# SC8701_EVM_RE0.net
KiCad netlist of a schematic drawn in Altium Designer
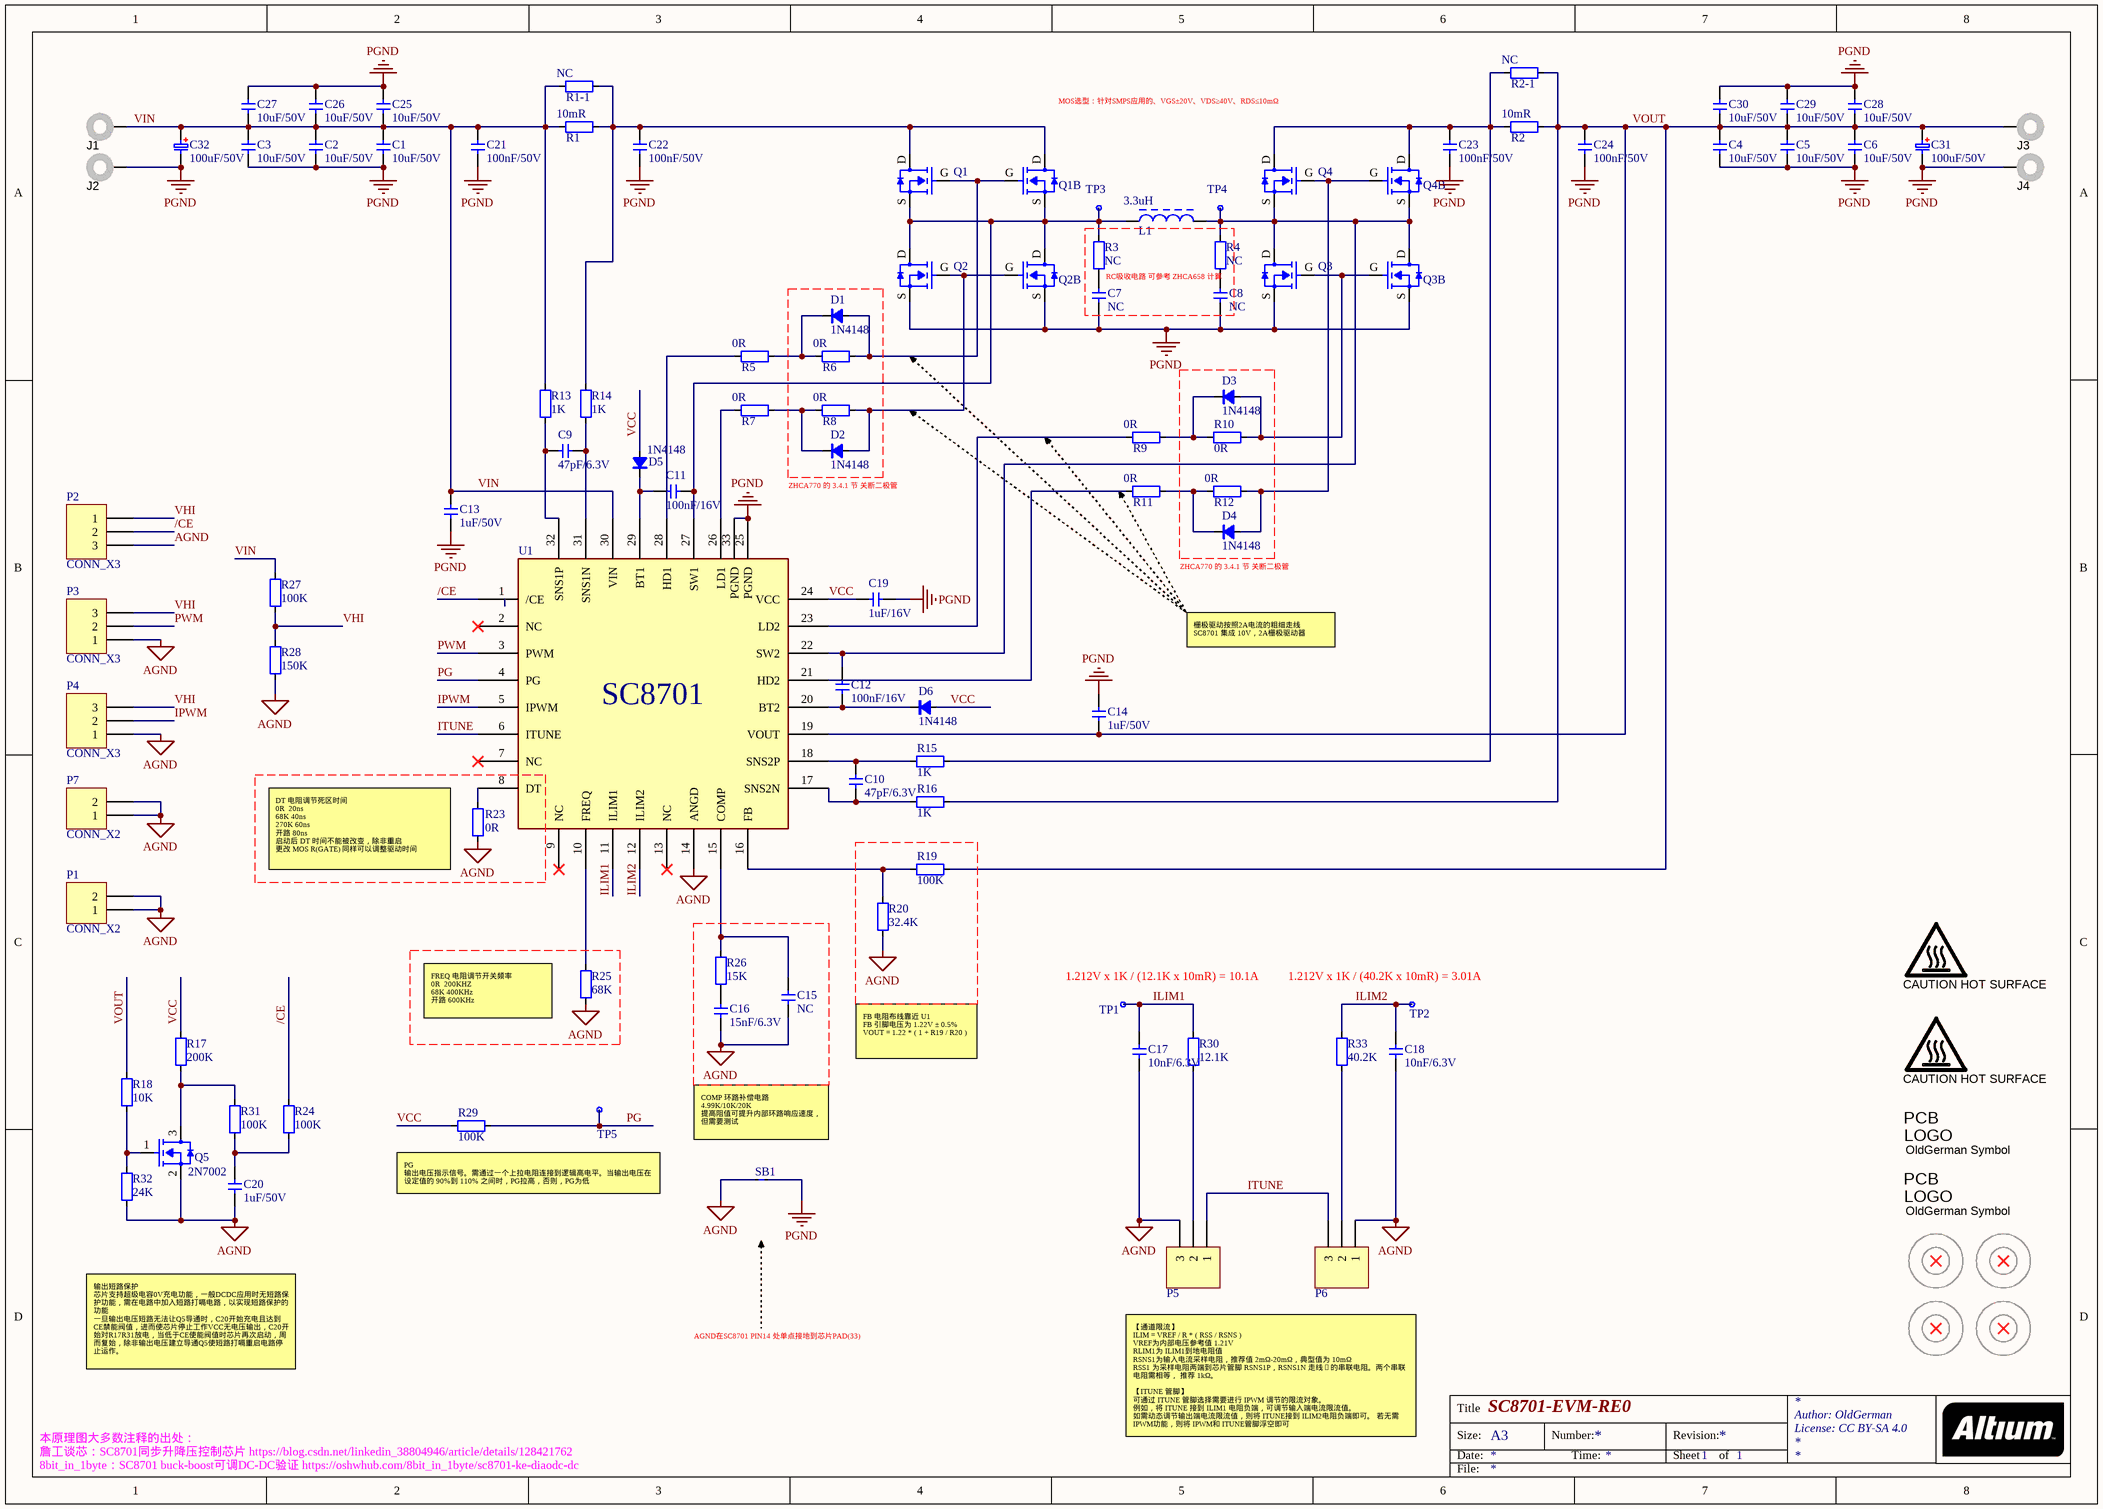
[diagram p0: SC8701_EVM_RE0.SchDoc]

(export (version "E")
  (design (tool "Eeschema 10.0.6"))
  (components
    (comp (ref "C1")
      (value "10uF/50V")
      (footprint "C1206")
      (description "Capacitor")
      (libsource (lib "ODG_AD_Lib") (part "CAP"))
    )
    (comp (ref "C2")
      (value "10uF/50V")
      (footprint "C1206")
      (description "Capacitor")
      (libsource (lib "ODG_AD_Lib") (part "CAP"))
    )
    (comp (ref "C3")
      (value "10uF/50V")
      (footprint "C1206")
      (description "Capacitor")
      (libsource (lib "ODG_AD_Lib") (part "CAP"))
    )
    (comp (ref "C4")
      (value "10uF/50V")
      (footprint "C1206")
      (description "Capacitor")
      (libsource (lib "ODG_AD_Lib") (part "CAP"))
    )
    (comp (ref "C5")
      (value "10uF/50V")
      (footprint "C1206")
      (description "Capacitor")
      (libsource (lib "ODG_AD_Lib") (part "CAP"))
    )
    (comp (ref "C6")
      (value "10uF/50V")
      (footprint "C1206")
      (description "Capacitor")
      (libsource (lib "ODG_AD_Lib") (part "CAP"))
    )
    (comp (ref "C7")
      (value "NC")
      (footprint "C0603")
      (description "Capacitor")
      (libsource (lib "ODG_AD_Lib") (part "CAP"))
    )
    (comp (ref "C8")
      (value "NC")
      (footprint "C0603")
      (description "Capacitor")
      (libsource (lib "ODG_AD_Lib") (part "CAP"))
    )
    (comp (ref "C9")
      (value "47pF/6.3V")
      (footprint "C0603")
      (description "Capacitor")
      (libsource (lib "ODG_AD_Lib") (part "CAP"))
    )
    (comp (ref "C10")
      (value "47pF/6.3V")
      (footprint "C0603")
      (description "Capacitor")
      (libsource (lib "ODG_AD_Lib") (part "CAP"))
    )
    (comp (ref "C11")
      (value "100nF/16V")
      (footprint "C0603")
      (description "Capacitor")
      (libsource (lib "ODG_AD_Lib") (part "CAP"))
    )
    (comp (ref "C12")
      (value "100nF/16V")
      (footprint "C0603")
      (description "Capacitor")
      (libsource (lib "ODG_AD_Lib") (part "CAP"))
    )
    (comp (ref "C13")
      (value "1uF/50V")
      (footprint "C0603")
      (description "Capacitor")
      (libsource (lib "ODG_AD_Lib") (part "CAP"))
    )
    (comp (ref "C14")
      (value "1uF/50V")
      (footprint "C0603")
      (description "Capacitor")
      (libsource (lib "ODG_AD_Lib") (part "CAP"))
    )
    (comp (ref "C15")
      (value "NC")
      (footprint "C0603")
      (description "Capacitor")
      (libsource (lib "ODG_AD_Lib") (part "CAP"))
    )
    (comp (ref "C16")
      (value "15nF/6.3V")
      (footprint "C0603")
      (description "Capacitor")
      (libsource (lib "ODG_AD_Lib") (part "CAP"))
    )
    (comp (ref "C17")
      (value "10nF/6.3V")
      (footprint "C0603")
      (description "Capacitor")
      (libsource (lib "ODG_AD_Lib") (part "CAP"))
    )
    (comp (ref "C18")
      (value "10nF/6.3V")
      (footprint "C0603")
      (description "Capacitor")
      (libsource (lib "ODG_AD_Lib") (part "CAP"))
    )
    (comp (ref "C19")
      (value "1uF/16V")
      (footprint "C0603")
      (description "Capacitor")
      (libsource (lib "ODG_AD_Lib") (part "CAP"))
    )
    (comp (ref "C20")
      (value "1uF/50V")
      (footprint "C0603")
      (description "Capacitor")
      (libsource (lib "ODG_AD_Lib") (part "CAP"))
    )
    (comp (ref "C21")
      (value "100nF/50V")
      (footprint "C0603")
      (description "Capacitor")
      (libsource (lib "ODG_AD_Lib") (part "CAP"))
    )
    (comp (ref "C22")
      (value "100nF/50V")
      (footprint "C0603")
      (description "Capacitor")
      (libsource (lib "ODG_AD_Lib") (part "CAP"))
    )
    (comp (ref "C23")
      (value "100nF/50V")
      (footprint "C0603")
      (description "Capacitor")
      (libsource (lib "ODG_AD_Lib") (part "CAP"))
    )
    (comp (ref "C24")
      (value "100nF/50V")
      (footprint "C0603")
      (description "Capacitor")
      (libsource (lib "ODG_AD_Lib") (part "CAP"))
    )
    (comp (ref "C25")
      (value "10uF/50V")
      (footprint "C1206")
      (description "Capacitor")
      (libsource (lib "ODG_AD_Lib") (part "CAP"))
    )
    (comp (ref "C26")
      (value "10uF/50V")
      (footprint "C1206")
      (description "Capacitor")
      (libsource (lib "ODG_AD_Lib") (part "CAP"))
    )
    (comp (ref "C27")
      (value "10uF/50V")
      (footprint "C1206")
      (description "Capacitor")
      (libsource (lib "ODG_AD_Lib") (part "CAP"))
    )
    (comp (ref "C28")
      (value "10uF/50V")
      (footprint "C1206")
      (description "Capacitor")
      (libsource (lib "ODG_AD_Lib") (part "CAP"))
    )
    (comp (ref "C29")
      (value "10uF/50V")
      (footprint "C1206")
      (description "Capacitor")
      (libsource (lib "ODG_AD_Lib") (part "CAP"))
    )
    (comp (ref "C30")
      (value "10uF/50V")
      (footprint "C1206")
      (description "Capacitor")
      (libsource (lib "ODG_AD_Lib") (part "CAP"))
    )
    (comp (ref "C31")
      (value "100uF/50V")
      (footprint "CAP OS-CON D=10.0 L=10.0 F10")
      (description "Capacitor")
      (libsource (lib "ODG_AD_Lib") (part "CAP_Polar_Aluminum"))
    )
    (comp (ref "C32")
      (value "100uF/50V")
      (footprint "CAP OS-CON D=10.0 L=10.0 F10")
      (description "Capacitor")
      (libsource (lib "ODG_AD_Lib") (part "CAP_Polar_Aluminum"))
    )
    (comp (ref "D1")
      (value "1N4148")
      (footprint "SOD-323")
      (description "二极管")
      (libsource (lib "ODG_AD_Lib") (part "DIODE"))
    )
    (comp (ref "D2")
      (value "1N4148")
      (footprint "SOD-323")
      (description "二极管")
      (libsource (lib "ODG_AD_Lib") (part "DIODE"))
    )
    (comp (ref "D3")
      (value "1N4148")
      (footprint "SOD-323")
      (description "二极管")
      (libsource (lib "ODG_AD_Lib") (part "DIODE"))
    )
    (comp (ref "D4")
      (value "1N4148")
      (footprint "SOD-323")
      (description "二极管")
      (libsource (lib "ODG_AD_Lib") (part "DIODE"))
    )
    (comp (ref "D5")
      (value "1N4148")
      (footprint "SOD-323")
      (description "二极管")
      (libsource (lib "") (part "DIODE_1"))
    )
    (comp (ref "D6")
      (value "1N4148")
      (footprint "SOD-323")
      (description "二极管")
      (libsource (lib "ODG_AD_Lib") (part "DIODE"))
    )
    (comp (ref "H1") (value "HOLE") (footprint "M3.2 D=8") (libsource (lib "ODG_AD_Lib") (part "HOLE")))
    (comp (ref "H2") (value "HOLE") (footprint "M3.2 D=8") (libsource (lib "ODG_AD_Lib") (part "HOLE")))
    (comp (ref "H3") (value "HOLE") (footprint "M3.2 D=8") (libsource (lib "ODG_AD_Lib") (part "HOLE")))
    (comp (ref "H4") (value "HOLE") (footprint "M3.2 D=8") (libsource (lib "ODG_AD_Lib") (part "HOLE")))
    (comp (ref "J1")
      (value "U6047")
      (footprint "JACK_BANANA_U6047")
      (description "Banana Jack")
      (fields
        (field (name "PARTNUMBER") "575-8")
        (field (name "MANUFACTURER") "Keystone")
        (field (name "PUBLISHER") "Texas Instruments")
      )
      (libsource (lib "ODG_AD_Lib") (part "JACK_BANANA"))
    )
    (comp (ref "J2")
      (value "U6047")
      (footprint "JACK_BANANA_U6047")
      (description "Banana Jack")
      (fields
        (field (name "PARTNUMBER") "575-8")
        (field (name "MANUFACTURER") "Keystone")
        (field (name "PUBLISHER") "Texas Instruments")
      )
      (libsource (lib "ODG_AD_Lib") (part "JACK_BANANA"))
    )
    (comp (ref "J3")
      (value "U6047")
      (footprint "JACK_BANANA_U6047")
      (description "Banana Jack")
      (fields
        (field (name "PARTNUMBER") "575-8")
        (field (name "MANUFACTURER") "Keystone")
        (field (name "PUBLISHER") "Texas Instruments")
      )
      (libsource (lib "ODG_AD_Lib") (part "JACK_BANANA"))
    )
    (comp (ref "J4")
      (value "U6047")
      (footprint "JACK_BANANA_U6047")
      (description "Banana Jack")
      (fields
        (field (name "PARTNUMBER") "575-8")
        (field (name "MANUFACTURER") "Keystone")
        (field (name "PUBLISHER") "Texas Instruments")
      )
      (libsource (lib "ODG_AD_Lib") (part "JACK_BANANA"))
    )
    (comp (ref "L1")
      (value "3.3uH")
      (footprint "INDUCTOR 1350 12.6X13.5X5.0mm")
      (description "135 功率电感 额定电流15A")
      (libsource (lib "ODG_AD_Lib") (part "Inductor_power"))
    )
    (comp (ref "LOGO1")
      (value "CAUTION HOT SURFACE")
      (footprint "IEC_HotSurface_Small")
      (description "IEC 61010-1 Hot Surface Warning")
      (fields (field (name "SYMBOLCREATOR") "a0412235") (field (name "PUBLISHER") "Texas Instruments"))
      (libsource (lib "ODG_AD_Lib") (part "IEC_HotSurface"))
    )
    (comp (ref "LOGO2")
      (value "CAUTION HOT SURFACE")
      (footprint "IEC_HotSurface_Small")
      (description "IEC 61010-1 Hot Surface Warning")
      (fields (field (name "SYMBOLCREATOR") "a0412235") (field (name "PUBLISHER") "Texas Instruments"))
      (libsource (lib "ODG_AD_Lib") (part "IEC_HotSurface"))
    )
    (comp (ref "Logo3")
      (value "OldGerman Symbol")
      (footprint "ODG_LOGO")
      (fields (field (name "SYMBOLCREATOR") "a0412235") (field (name "PUBLISHER") "Texas Instruments"))
      (libsource (lib "ODG_AD_Lib") (part "OldGeman"))
    )
    (comp (ref "Logo4")
      (value "OldGerman Symbol")
      (footprint "ODG_LOGO")
      (fields (field (name "SYMBOLCREATOR") "a0412235") (field (name "PUBLISHER") "Texas Instruments"))
      (libsource (lib "ODG_AD_Lib") (part "OldGeman"))
    )
    (comp (ref "P1")
      (value "CONN_X2")
      (footprint "2.54mm_Male_x2")
      (libsource (lib "ODG_AD_Lib") (part "CONN_X2"))
    )
    (comp (ref "P2")
      (value "CONN_X3")
      (footprint "2.54mm_Male_x3")
      (libsource (lib "ODG_AD_Lib") (part "CONN_X3"))
    )
    (comp (ref "P3") (value "CONN_X3") (footprint "2.54mm_Male_x3") (libsource (lib "") (part "CONN_X3_1")))
    (comp (ref "P4") (value "CONN_X3") (footprint "2.54mm_Male_x3") (libsource (lib "") (part "CONN_X3_1")))
    (comp (ref "P5")
      (value "CONN_X3")
      (footprint "2.54mm_Male_x3")
      (libsource (lib "ODG_AD_Lib") (part "CONN_X3"))
    )
    (comp (ref "P6")
      (value "CONN_X3")
      (footprint "2.54mm_Male_x3")
      (libsource (lib "ODG_AD_Lib") (part "CONN_X3"))
    )
    (comp (ref "P7")
      (value "CONN_X2")
      (footprint "2.54mm_Male_x2")
      (libsource (lib "ODG_AD_Lib") (part "CONN_X2"))
    )
    (comp (ref "Q1")
      (value "N-MOS_GDS")
      (footprint "SON 3X3 NexFET Q3")
      (libsource (lib "ODG_AD_Lib") (part "N-MOS_GDS"))
    )
    (comp (ref "Q1B")
      (value "N-MOS_GDS")
      (footprint "SO8FL ROUND")
      (libsource (lib "ODG_AD_Lib") (part "N-MOS_GDS"))
    )
    (comp (ref "Q2")
      (value "N-MOS_GDS")
      (footprint "SON 3X3 NexFET Q3")
      (libsource (lib "ODG_AD_Lib") (part "N-MOS_GDS"))
    )
    (comp (ref "Q2B")
      (value "N-MOS_GDS")
      (footprint "SO8FL ROUND")
      (libsource (lib "ODG_AD_Lib") (part "N-MOS_GDS"))
    )
    (comp (ref "Q3")
      (value "N-MOS_GDS")
      (footprint "SON 3X3 NexFET Q3")
      (libsource (lib "ODG_AD_Lib") (part "N-MOS_GDS"))
    )
    (comp (ref "Q3B")
      (value "N-MOS_GDS")
      (footprint "SO8FL ROUND")
      (libsource (lib "ODG_AD_Lib") (part "N-MOS_GDS"))
    )
    (comp (ref "Q4")
      (value "N-MOS_GDS")
      (footprint "SON 3X3 NexFET Q3")
      (libsource (lib "ODG_AD_Lib") (part "N-MOS_GDS"))
    )
    (comp (ref "Q4B")
      (value "N-MOS_GDS")
      (footprint "SO8FL ROUND")
      (libsource (lib "ODG_AD_Lib") (part "N-MOS_GDS"))
    )
    (comp (ref "Q5")
      (value "2N7002")
      (footprint "INFINEON SOT-23-3")
      (description "N-MOS")
      (libsource (lib "ODG_AD_Lib") (part "N-MOS_123"))
    )
    (comp (ref "R1")
      (value "10mR")
      (footprint "R1206")
      (description "IEC Standard")
      (libsource (lib "ODG_AD_Lib") (part "RES"))
    )
    (comp (ref "R1-1")
      (value "NC")
      (footprint "R1206")
      (description "IEC Standard")
      (libsource (lib "ODG_AD_Lib") (part "RES"))
    )
    (comp (ref "R2")
      (value "10mR")
      (footprint "R1206")
      (description "IEC Standard")
      (libsource (lib "ODG_AD_Lib") (part "RES"))
    )
    (comp (ref "R2-1")
      (value "NC")
      (footprint "R1206")
      (description "IEC Standard")
      (libsource (lib "ODG_AD_Lib") (part "RES"))
    )
    (comp (ref "R3")
      (value "NC")
      (footprint "R0805")
      (description "IEC Standard")
      (libsource (lib "") (part "RES_1"))
    )
    (comp (ref "R4")
      (value "NC")
      (footprint "R0805")
      (description "IEC Standard")
      (libsource (lib "") (part "RES_1"))
    )
    (comp (ref "R5")
      (value "0R")
      (footprint "R0603")
      (description "IEC Standard")
      (libsource (lib "ODG_AD_Lib") (part "RES"))
    )
    (comp (ref "R6")
      (value "0R")
      (footprint "R0603")
      (description "IEC Standard")
      (libsource (lib "ODG_AD_Lib") (part "RES"))
    )
    (comp (ref "R7")
      (value "0R")
      (footprint "R0603")
      (description "IEC Standard")
      (libsource (lib "ODG_AD_Lib") (part "RES"))
    )
    (comp (ref "R8")
      (value "0R")
      (footprint "R0603")
      (description "IEC Standard")
      (libsource (lib "ODG_AD_Lib") (part "RES"))
    )
    (comp (ref "R9")
      (value "0R")
      (footprint "R0603")
      (description "IEC Standard")
      (libsource (lib "ODG_AD_Lib") (part "RES"))
    )
    (comp (ref "R10")
      (value "0R")
      (footprint "R0603")
      (description "IEC Standard")
      (libsource (lib "ODG_AD_Lib") (part "RES"))
    )
    (comp (ref "R11")
      (value "0R")
      (footprint "R0603")
      (description "IEC Standard")
      (libsource (lib "ODG_AD_Lib") (part "RES"))
    )
    (comp (ref "R12")
      (value "0R")
      (footprint "R0603")
      (description "IEC Standard")
      (libsource (lib "ODG_AD_Lib") (part "RES"))
    )
    (comp (ref "R13")
      (value "1K")
      (footprint "R0603")
      (description "IEC Standard")
      (libsource (lib "") (part "RES_1"))
    )
    (comp (ref "R14")
      (value "1K")
      (footprint "R0603")
      (description "IEC Standard")
      (libsource (lib "") (part "RES_1"))
    )
    (comp (ref "R15")
      (value "1K")
      (footprint "R0603")
      (description "IEC Standard")
      (libsource (lib "") (part "RES_2"))
    )
    (comp (ref "R16")
      (value "1K")
      (footprint "R0603")
      (description "IEC Standard")
      (libsource (lib "") (part "RES_2"))
    )
    (comp (ref "R17")
      (value "200K")
      (footprint "R0603")
      (description "IEC Standard")
      (libsource (lib "") (part "RES_1"))
    )
    (comp (ref "R18")
      (value "10K")
      (footprint "R0603")
      (description "IEC Standard")
      (libsource (lib "") (part "RES_1"))
    )
    (comp (ref "R19")
      (value "100K")
      (footprint "R0603")
      (description "IEC Standard")
      (libsource (lib "ODG_AD_Lib") (part "RES"))
    )
    (comp (ref "R20")
      (value "32.4K")
      (footprint "R0603")
      (description "IEC Standard")
      (libsource (lib "") (part "RES_1"))
    )
    (comp (ref "R23")
      (value "0R")
      (footprint "R0603")
      (description "IEC Standard")
      (libsource (lib "") (part "RES_1"))
    )
    (comp (ref "R24")
      (value "100K")
      (footprint "R0603")
      (description "IEC Standard")
      (libsource (lib "") (part "RES_1"))
    )
    (comp (ref "R25")
      (value "68K")
      (footprint "R0603")
      (description "IEC Standard")
      (libsource (lib "") (part "RES_1"))
    )
    (comp (ref "R26")
      (value "15K")
      (footprint "R0603")
      (description "IEC Standard")
      (libsource (lib "") (part "RES_1"))
    )
    (comp (ref "R27")
      (value "100K")
      (footprint "R0603")
      (description "IEC Standard")
      (libsource (lib "") (part "RES_1"))
    )
    (comp (ref "R28")
      (value "150K")
      (footprint "R0603")
      (description "IEC Standard")
      (libsource (lib "") (part "RES_1"))
    )
    (comp (ref "R29")
      (value "100K")
      (footprint "R0603")
      (description "IEC Standard")
      (libsource (lib "ODG_AD_Lib") (part "RES"))
    )
    (comp (ref "R30")
      (value "12.1K")
      (footprint "R0603")
      (description "IEC Standard")
      (libsource (lib "") (part "RES_1"))
    )
    (comp (ref "R31")
      (value "100K")
      (footprint "R0603")
      (description "IEC Standard")
      (libsource (lib "") (part "RES_1"))
    )
    (comp (ref "R32")
      (value "24K")
      (footprint "R0603")
      (description "IEC Standard")
      (libsource (lib "") (part "RES_1"))
    )
    (comp (ref "R33")
      (value "40.2K")
      (footprint "R0603")
      (description "IEC Standard")
      (libsource (lib "") (part "RES_1"))
    )
    (comp (ref "SB1")
      (value "NetTie_200um")
      (footprint "NetTie_200um")
      (description "Net Tie")
      (fields (field (name "PART NUMBER") "NetTie 0.2mm") (field (name "PUBLISHER") "Nordic Semiconductor"))
      (libsource (lib "pca63100") (part "NetTie 0.2mm"))
    )
    (comp (ref "TP1")
      (value "CONN_X1_DOT")
      (footprint "2.54mm_Male_x1")
      (libsource (lib "ODG_AD_Lib") (part "CONN_X1_DOT"))
    )
    (comp (ref "TP2")
      (value "CONN_X1_DOT")
      (footprint "2.54mm_Male_x1")
      (libsource (lib "ODG_AD_Lib") (part "CONN_X1_DOT"))
    )
    (comp (ref "TP3")
      (value "CONN_X1_DOT")
      (footprint "2.54mm_Male_x1")
      (libsource (lib "ODG_AD_Lib") (part "CONN_X1_DOT"))
    )
    (comp (ref "TP4")
      (value "CONN_X1_DOT")
      (footprint "2.54mm_Male_x1")
      (libsource (lib "ODG_AD_Lib") (part "CONN_X1_DOT"))
    )
    (comp (ref "TP5")
      (value "CONN_X1_DOT")
      (footprint "2.54mm_Male_x1")
      (libsource (lib "ODG_AD_Lib") (part "CONN_X1_DOT"))
    )
    (comp (ref "U1")
      (value "SC8701 (A)")
      (footprint "TQFN-32 4X4MM 0.4 VIA")
      (description "高效率, 同步, 4 管升降压控制器")
      (libsource (lib "ODG_AD_Lib") (part "SC8701 (A)"))
    )
  )
  (nets
    (net (code "1") (name "/ILIM1") (class "Default")
      (node (ref "C17") (pin "2") (pinfunction "2_2") (pintype "passive"))
      (node (ref "R30") (pin "2") (pinfunction "2_2") (pintype "passive"))
      (node (ref "TP1") (pin "1") (pinfunction "1_1") (pintype "passive"))
      (node (ref "U1") (pin "11") (pinfunction "ILIM1_11") (pintype "passive"))
    )
    (net (code "2") (name "/ILIM2") (class "Default")
      (node (ref "C18") (pin "2") (pinfunction "2_2") (pintype "passive"))
      (node (ref "R33") (pin "2") (pinfunction "2_2") (pintype "passive"))
      (node (ref "TP2") (pin "1") (pinfunction "1_1") (pintype "passive"))
      (node (ref "U1") (pin "12") (pinfunction "ILIM2_12") (pintype "passive"))
    )
    (net (code "3") (name "/IPWM") (class "Default")
      (node (ref "P4") (pin "2") (pinfunction "2_2") (pintype "passive"))
      (node (ref "U1") (pin "5") (pinfunction "IPWM_5") (pintype "passive"))
    )
    (net (code "4") (name "/ITUNE") (class "Default")
      (node (ref "P5") (pin "1") (pinfunction "1_1") (pintype "passive"))
      (node (ref "P6") (pin "3") (pinfunction "3_3") (pintype "passive"))
      (node (ref "U1") (pin "6") (pinfunction "ITUNE_6") (pintype "passive"))
    )
    (net (code "5") (name "/PG") (class "Default")
      (node (ref "R29") (pin "2") (pinfunction "2_2") (pintype "passive"))
      (node (ref "TP5") (pin "1") (pinfunction "1_1") (pintype "passive"))
      (node (ref "U1") (pin "4") (pinfunction "PG_4") (pintype "passive"))
    )
    (net (code "6") (name "/PWM") (class "Default")
      (node (ref "P3") (pin "2") (pinfunction "2_2") (pintype "passive"))
      (node (ref "U1") (pin "3") (pinfunction "PWM_3") (pintype "passive"))
    )
    (net (code "7") (name "/VCC") (class "Default")
      (node (ref "C19") (pin "1") (pinfunction "1_1") (pintype "passive"))
      (node (ref "D5") (pin "1") (pinfunction "A_1") (pintype "passive"))
      (node (ref "D6") (pin "1") (pinfunction "A_1") (pintype "passive"))
      (node (ref "R17") (pin "2") (pinfunction "2_2") (pintype "passive"))
      (node (ref "R29") (pin "1") (pinfunction "1_1") (pintype "passive"))
      (node (ref "U1") (pin "24") (pinfunction "VCC_24") (pintype "passive"))
    )
    (net (code "8") (name "/VHI") (class "Default")
      (node (ref "P2") (pin "1") (pinfunction "1_1") (pintype "passive"))
      (node (ref "P3") (pin "3") (pinfunction "3_3") (pintype "passive"))
      (node (ref "P4") (pin "3") (pinfunction "3_3") (pintype "passive"))
      (node (ref "R27") (pin "1") (pinfunction "1_1") (pintype "passive"))
      (node (ref "R28") (pin "2") (pinfunction "2_2") (pintype "passive"))
    )
    (net (code "9") (name "/VIN") (class "Default")
      (node (ref "C1") (pin "2") (pinfunction "2_2") (pintype "passive"))
      (node (ref "C13") (pin "1") (pinfunction "1_1") (pintype "passive"))
      (node (ref "C2") (pin "2") (pinfunction "2_2") (pintype "passive"))
      (node (ref "C21") (pin "2") (pinfunction "2_2") (pintype "passive"))
      (node (ref "C25") (pin "2") (pinfunction "2_2") (pintype "passive"))
      (node (ref "C26") (pin "2") (pinfunction "2_2") (pintype "passive"))
      (node (ref "C27") (pin "2") (pinfunction "2_2") (pintype "passive"))
      (node (ref "C3") (pin "2") (pinfunction "2_2") (pintype "passive"))
      (node (ref "C32") (pin "1") (pinfunction "1_1") (pintype "passive"))
      (node (ref "J1") (pin "1") (pinfunction "1_1") (pintype "passive"))
      (node (ref "R1") (pin "1") (pinfunction "1_1") (pintype "passive"))
      (node (ref "R1-1") (pin "1") (pinfunction "1_1") (pintype "passive"))
      (node (ref "R13") (pin "2") (pinfunction "2_2") (pintype "passive"))
      (node (ref "R27") (pin "2") (pinfunction "2_2") (pintype "passive"))
      (node (ref "U1") (pin "30") (pinfunction "VIN_30") (pintype "passive"))
    )
    (net (code "10") (name "/VOUT") (class "Default")
      (node (ref "C14") (pin "1") (pinfunction "1_1") (pintype "passive"))
      (node (ref "C24") (pin "2") (pinfunction "2_2") (pintype "passive"))
      (node (ref "C28") (pin "2") (pinfunction "2_2") (pintype "passive"))
      (node (ref "C29") (pin "2") (pinfunction "2_2") (pintype "passive"))
      (node (ref "C30") (pin "2") (pinfunction "2_2") (pintype "passive"))
      (node (ref "C31") (pin "1") (pinfunction "1_1") (pintype "passive"))
      (node (ref "C4") (pin "2") (pinfunction "2_2") (pintype "passive"))
      (node (ref "C5") (pin "2") (pinfunction "2_2") (pintype "passive"))
      (node (ref "C6") (pin "2") (pinfunction "2_2") (pintype "passive"))
      (node (ref "J3") (pin "1") (pinfunction "1_1") (pintype "passive"))
      (node (ref "R16") (pin "1") (pinfunction "1_1") (pintype "passive"))
      (node (ref "R18") (pin "2") (pinfunction "2_2") (pintype "passive"))
      (node (ref "R19") (pin "2") (pinfunction "2_2") (pintype "passive"))
      (node (ref "R2") (pin "2") (pinfunction "2_2") (pintype "passive"))
      (node (ref "R2-1") (pin "2") (pinfunction "2_2") (pintype "passive"))
      (node (ref "U1") (pin "19") (pinfunction "VOUT_19") (pintype "passive"))
    )
    (net (code "11") (name "/{slash}CE") (class "Default")
      (node (ref "P2") (pin "2") (pinfunction "2_2") (pintype "passive"))
      (node (ref "R24") (pin "2") (pinfunction "2_2") (pintype "passive"))
      (node (ref "U1") (pin "1") (pinfunction "/CE_1") (pintype "passive"))
    )
    (net (code "12") (name "AGND") (class "Default")
      (node (ref "C15") (pin "1") (pinfunction "1_1") (pintype "passive"))
      (node (ref "C16") (pin "1") (pinfunction "1_1") (pintype "passive"))
      (node (ref "C17") (pin "1") (pinfunction "1_1") (pintype "passive"))
      (node (ref "C18") (pin "1") (pinfunction "1_1") (pintype "passive"))
      (node (ref "C20") (pin "2") (pinfunction "2_2") (pintype "passive"))
      (node (ref "P1") (pin "1") (pinfunction "1_1") (pintype "passive"))
      (node (ref "P1") (pin "2") (pinfunction "2_2") (pintype "passive"))
      (node (ref "P2") (pin "3") (pinfunction "3_3") (pintype "passive"))
      (node (ref "P3") (pin "1") (pinfunction "1_1") (pintype "passive"))
      (node (ref "P4") (pin "1") (pinfunction "1_1") (pintype "passive"))
      (node (ref "P5") (pin "3") (pinfunction "3_3") (pintype "passive"))
      (node (ref "P6") (pin "1") (pinfunction "1_1") (pintype "passive"))
      (node (ref "P7") (pin "1") (pinfunction "1_1") (pintype "passive"))
      (node (ref "P7") (pin "2") (pinfunction "2_2") (pintype "passive"))
      (node (ref "Q5") (pin "2") (pinfunction "S_2") (pintype "passive"))
      (node (ref "R20") (pin "1") (pinfunction "1_1") (pintype "passive"))
      (node (ref "R23") (pin "1") (pinfunction "1_1") (pintype "passive"))
      (node (ref "R25") (pin "1") (pinfunction "1_1") (pintype "passive"))
      (node (ref "R28") (pin "1") (pinfunction "1_1") (pintype "passive"))
      (node (ref "R32") (pin "1") (pinfunction "1_1") (pintype "passive"))
      (node (ref "SB1") (pin "1") (pinfunction "1_1") (pintype "passive"))
      (node (ref "U1") (pin "14") (pinfunction "ANGD_14") (pintype "passive"))
    )
    (net (code "13") (name "Net-(C7-Pad2)") (class "Default")
      (node (ref "C7") (pin "2") (pinfunction "2_2") (pintype "passive"))
      (node (ref "R3") (pin "1") (pinfunction "1_1") (pintype "passive"))
    )
    (net (code "14") (name "Net-(C8-Pad2)") (class "Default")
      (node (ref "C8") (pin "2") (pinfunction "2_2") (pintype "passive"))
      (node (ref "R4") (pin "1") (pinfunction "1_1") (pintype "passive"))
    )
    (net (code "15") (name "Net-(C16-Pad2)") (class "Default")
      (node (ref "C16") (pin "2") (pinfunction "2_2") (pintype "passive"))
      (node (ref "R26") (pin "1") (pinfunction "1_1") (pintype "passive"))
    )
    (net (code "16") (name "Net-(C20-Pad1)") (class "Default")
      (node (ref "C20") (pin "1") (pinfunction "1_1") (pintype "passive"))
      (node (ref "R24") (pin "1") (pinfunction "1_1") (pintype "passive"))
      (node (ref "R31") (pin "1") (pinfunction "1_1") (pintype "passive"))
    )
    (net (code "17") (name "Net-(C22-Pad2)") (class "Default")
      (node (ref "C22") (pin "2") (pinfunction "2_2") (pintype "passive"))
      (node (ref "Q1") (pin "D") (pinfunction "D_D") (pintype "passive"))
      (node (ref "Q1B") (pin "D") (pinfunction "D_D") (pintype "passive"))
      (node (ref "R1") (pin "2") (pinfunction "2_2") (pintype "passive"))
      (node (ref "R1-1") (pin "2") (pinfunction "2_2") (pintype "passive"))
      (node (ref "R14") (pin "2") (pinfunction "2_2") (pintype "passive"))
    )
    (net (code "18") (name "Net-(C23-Pad2)") (class "Default")
      (node (ref "C23") (pin "2") (pinfunction "2_2") (pintype "passive"))
      (node (ref "Q4") (pin "D") (pinfunction "D_D") (pintype "passive"))
      (node (ref "Q4B") (pin "D") (pinfunction "D_D") (pintype "passive"))
      (node (ref "R15") (pin "1") (pinfunction "1_1") (pintype "passive"))
      (node (ref "R2") (pin "1") (pinfunction "1_1") (pintype "passive"))
      (node (ref "R2-1") (pin "1") (pinfunction "1_1") (pintype "passive"))
    )
    (net (code "19") (name "Net-(D1-A)") (class "Default")
      (node (ref "D1") (pin "1") (pinfunction "A_1") (pintype "passive"))
      (node (ref "Q1") (pin "G") (pinfunction "G_G") (pintype "passive"))
      (node (ref "Q1B") (pin "G") (pinfunction "G_G") (pintype "passive"))
      (node (ref "R6") (pin "2") (pinfunction "2_2") (pintype "passive"))
    )
    (net (code "20") (name "Net-(D1-C)") (class "Default")
      (node (ref "D1") (pin "2") (pinfunction "C_2") (pintype "passive"))
      (node (ref "R5") (pin "2") (pinfunction "2_2") (pintype "passive"))
      (node (ref "R6") (pin "1") (pinfunction "1_1") (pintype "passive"))
    )
    (net (code "21") (name "Net-(D2-A)") (class "Default")
      (node (ref "D2") (pin "1") (pinfunction "A_1") (pintype "passive"))
      (node (ref "Q2") (pin "G") (pinfunction "G_G") (pintype "passive"))
      (node (ref "Q2B") (pin "G") (pinfunction "G_G") (pintype "passive"))
      (node (ref "R8") (pin "2") (pinfunction "2_2") (pintype "passive"))
    )
    (net (code "22") (name "Net-(D2-C)") (class "Default")
      (node (ref "D2") (pin "2") (pinfunction "C_2") (pintype "passive"))
      (node (ref "R7") (pin "2") (pinfunction "2_2") (pintype "passive"))
      (node (ref "R8") (pin "1") (pinfunction "1_1") (pintype "passive"))
    )
    (net (code "23") (name "Net-(D3-A)") (class "Default")
      (node (ref "D3") (pin "1") (pinfunction "A_1") (pintype "passive"))
      (node (ref "Q3") (pin "G") (pinfunction "G_G") (pintype "passive"))
      (node (ref "Q3B") (pin "G") (pinfunction "G_G") (pintype "passive"))
      (node (ref "R10") (pin "2") (pinfunction "2_2") (pintype "passive"))
    )
    (net (code "24") (name "Net-(D3-C)") (class "Default")
      (node (ref "D3") (pin "2") (pinfunction "C_2") (pintype "passive"))
      (node (ref "R10") (pin "1") (pinfunction "1_1") (pintype "passive"))
      (node (ref "R9") (pin "2") (pinfunction "2_2") (pintype "passive"))
    )
    (net (code "25") (name "Net-(D4-A)") (class "Default")
      (node (ref "D4") (pin "1") (pinfunction "A_1") (pintype "passive"))
      (node (ref "Q4") (pin "G") (pinfunction "G_G") (pintype "passive"))
      (node (ref "Q4B") (pin "G") (pinfunction "G_G") (pintype "passive"))
      (node (ref "R12") (pin "2") (pinfunction "2_2") (pintype "passive"))
    )
    (net (code "26") (name "Net-(D4-C)") (class "Default")
      (node (ref "D4") (pin "2") (pinfunction "C_2") (pintype "passive"))
      (node (ref "R11") (pin "2") (pinfunction "2_2") (pintype "passive"))
      (node (ref "R12") (pin "1") (pinfunction "1_1") (pintype "passive"))
    )
    (net (code "27") (name "Net-(D5-C)") (class "Default")
      (node (ref "C11") (pin "1") (pinfunction "1_1") (pintype "passive"))
      (node (ref "D5") (pin "2") (pinfunction "C_2") (pintype "passive"))
      (node (ref "U1") (pin "29") (pinfunction "BT1_29") (pintype "passive"))
    )
    (net (code "28") (name "Net-(D6-C)") (class "Default")
      (node (ref "C12") (pin "2") (pinfunction "2_2") (pintype "passive"))
      (node (ref "D6") (pin "2") (pinfunction "C_2") (pintype "passive"))
      (node (ref "U1") (pin "20") (pinfunction "BT2_20") (pintype "passive"))
    )
    (net (code "29") (name "Net-(P5-Pad2)") (class "Default")
      (node (ref "P5") (pin "2") (pinfunction "2_2") (pintype "passive"))
      (node (ref "R30") (pin "1") (pinfunction "1_1") (pintype "passive"))
    )
    (net (code "30") (name "Net-(P6-Pad2)") (class "Default")
      (node (ref "P6") (pin "2") (pinfunction "2_2") (pintype "passive"))
      (node (ref "R33") (pin "1") (pinfunction "1_1") (pintype "passive"))
    )
    (net (code "31") (name "Net-(Q5-D)") (class "Default")
      (node (ref "Q5") (pin "3") (pinfunction "D_3") (pintype "passive"))
      (node (ref "R17") (pin "1") (pinfunction "1_1") (pintype "passive"))
      (node (ref "R31") (pin "2") (pinfunction "2_2") (pintype "passive"))
    )
    (net (code "32") (name "Net-(Q5-G)") (class "Default")
      (node (ref "Q5") (pin "1") (pinfunction "G_1") (pintype "passive"))
      (node (ref "R18") (pin "1") (pinfunction "1_1") (pintype "passive"))
      (node (ref "R32") (pin "2") (pinfunction "2_2") (pintype "passive"))
    )
    (net (code "33") (name "Net-(U1-COMP)") (class "Default")
      (node (ref "C15") (pin "2") (pinfunction "2_2") (pintype "passive"))
      (node (ref "R26") (pin "2") (pinfunction "2_2") (pintype "passive"))
      (node (ref "U1") (pin "15") (pinfunction "COMP_15") (pintype "passive"))
    )
    (net (code "34") (name "Net-(U1-DT)") (class "Default")
      (node (ref "R23") (pin "2") (pinfunction "2_2") (pintype "passive"))
      (node (ref "U1") (pin "8") (pinfunction "DT_8") (pintype "passive"))
    )
    (net (code "35") (name "Net-(U1-FB)") (class "Default")
      (node (ref "R19") (pin "1") (pinfunction "1_1") (pintype "passive"))
      (node (ref "R20") (pin "2") (pinfunction "2_2") (pintype "passive"))
      (node (ref "U1") (pin "16") (pinfunction "FB_16") (pintype "passive"))
    )
    (net (code "36") (name "Net-(U1-FREQ)") (class "Default")
      (node (ref "R25") (pin "2") (pinfunction "2_2") (pintype "passive"))
      (node (ref "U1") (pin "10") (pinfunction "FREQ_10") (pintype "passive"))
    )
    (net (code "37") (name "Net-(U1-HD1)") (class "Default")
      (node (ref "R5") (pin "1") (pinfunction "1_1") (pintype "passive"))
      (node (ref "U1") (pin "28") (pinfunction "HD1_28") (pintype "passive"))
    )
    (net (code "38") (name "Net-(U1-HD2)") (class "Default")
      (node (ref "R11") (pin "1") (pinfunction "1_1") (pintype "passive"))
      (node (ref "U1") (pin "21") (pinfunction "HD2_21") (pintype "passive"))
    )
    (net (code "39") (name "Net-(U1-LD1)") (class "Default")
      (node (ref "R7") (pin "1") (pinfunction "1_1") (pintype "passive"))
      (node (ref "U1") (pin "26") (pinfunction "LD1_26") (pintype "passive"))
    )
    (net (code "40") (name "Net-(U1-LD2)") (class "Default")
      (node (ref "R9") (pin "1") (pinfunction "1_1") (pintype "passive"))
      (node (ref "U1") (pin "23") (pinfunction "LD2_23") (pintype "passive"))
    )
    (net (code "41") (name "Net-(U1-SNS1N)") (class "Default")
      (node (ref "C9") (pin "2") (pinfunction "2_2") (pintype "passive"))
      (node (ref "R14") (pin "1") (pinfunction "1_1") (pintype "passive"))
      (node (ref "U1") (pin "31") (pinfunction "SNS1N_31") (pintype "passive"))
    )
    (net (code "42") (name "Net-(U1-SNS1P)") (class "Default")
      (node (ref "C9") (pin "1") (pinfunction "1_1") (pintype "passive"))
      (node (ref "R13") (pin "1") (pinfunction "1_1") (pintype "passive"))
      (node (ref "U1") (pin "32") (pinfunction "SNS1P_32") (pintype "passive"))
    )
    (net (code "43") (name "Net-(U1-SNS2N)") (class "Default")
      (node (ref "C10") (pin "2") (pinfunction "2_2") (pintype "passive"))
      (node (ref "R16") (pin "2") (pinfunction "2_2") (pintype "passive"))
      (node (ref "U1") (pin "17") (pinfunction "SNS2N_17") (pintype "passive"))
    )
    (net (code "44") (name "Net-(U1-SNS2P)") (class "Default")
      (node (ref "C10") (pin "1") (pinfunction "1_1") (pintype "passive"))
      (node (ref "R15") (pin "2") (pinfunction "2_2") (pintype "passive"))
      (node (ref "U1") (pin "18") (pinfunction "SNS2P_18") (pintype "passive"))
    )
    (net (code "45") (name "Net-(U1-SW1)") (class "Default")
      (node (ref "C11") (pin "2") (pinfunction "2_2") (pintype "passive"))
      (node (ref "L1") (pin "1") (pintype "passive"))
      (node (ref "Q1") (pin "S") (pinfunction "S_S") (pintype "passive"))
      (node (ref "Q1B") (pin "S") (pinfunction "S_S") (pintype "passive"))
      (node (ref "Q2") (pin "D") (pinfunction "D_D") (pintype "passive"))
      (node (ref "Q2B") (pin "D") (pinfunction "D_D") (pintype "passive"))
      (node (ref "R3") (pin "2") (pinfunction "2_2") (pintype "passive"))
      (node (ref "TP3") (pin "1") (pinfunction "1_1") (pintype "passive"))
      (node (ref "U1") (pin "27") (pinfunction "SW1_27") (pintype "passive"))
    )
    (net (code "46") (name "Net-(U1-SW2)") (class "Default")
      (node (ref "C12") (pin "1") (pinfunction "1_1") (pintype "passive"))
      (node (ref "L1") (pin "2") (pinfunction "2_2") (pintype "passive"))
      (node (ref "Q3") (pin "D") (pinfunction "D_D") (pintype "passive"))
      (node (ref "Q3B") (pin "D") (pinfunction "D_D") (pintype "passive"))
      (node (ref "Q4") (pin "S") (pinfunction "S_S") (pintype "passive"))
      (node (ref "Q4B") (pin "S") (pinfunction "S_S") (pintype "passive"))
      (node (ref "R4") (pin "2") (pinfunction "2_2") (pintype "passive"))
      (node (ref "TP4") (pin "1") (pinfunction "1_1") (pintype "passive"))
      (node (ref "U1") (pin "22") (pinfunction "SW2_22") (pintype "passive"))
    )
    (net (code "47") (name "PGND") (class "Default")
      (node (ref "C1") (pin "1") (pinfunction "1_1") (pintype "passive"))
      (node (ref "C13") (pin "2") (pinfunction "2_2") (pintype "passive"))
      (node (ref "C14") (pin "2") (pinfunction "2_2") (pintype "passive"))
      (node (ref "C19") (pin "2") (pinfunction "2_2") (pintype "passive"))
      (node (ref "C2") (pin "1") (pinfunction "1_1") (pintype "passive"))
      (node (ref "C21") (pin "1") (pinfunction "1_1") (pintype "passive"))
      (node (ref "C22") (pin "1") (pinfunction "1_1") (pintype "passive"))
      (node (ref "C23") (pin "1") (pinfunction "1_1") (pintype "passive"))
      (node (ref "C24") (pin "1") (pinfunction "1_1") (pintype "passive"))
      (node (ref "C25") (pin "1") (pinfunction "1_1") (pintype "passive"))
      (node (ref "C26") (pin "1") (pinfunction "1_1") (pintype "passive"))
      (node (ref "C27") (pin "1") (pinfunction "1_1") (pintype "passive"))
      (node (ref "C28") (pin "1") (pinfunction "1_1") (pintype "passive"))
      (node (ref "C29") (pin "1") (pinfunction "1_1") (pintype "passive"))
      (node (ref "C3") (pin "1") (pinfunction "1_1") (pintype "passive"))
      (node (ref "C30") (pin "1") (pinfunction "1_1") (pintype "passive"))
      (node (ref "C31") (pin "2") (pinfunction "2_2") (pintype "passive"))
      (node (ref "C32") (pin "2") (pinfunction "2_2") (pintype "passive"))
      (node (ref "C4") (pin "1") (pinfunction "1_1") (pintype "passive"))
      (node (ref "C5") (pin "1") (pinfunction "1_1") (pintype "passive"))
      (node (ref "C6") (pin "1") (pinfunction "1_1") (pintype "passive"))
      (node (ref "C7") (pin "1") (pinfunction "1_1") (pintype "passive"))
      (node (ref "C8") (pin "1") (pinfunction "1_1") (pintype "passive"))
      (node (ref "J2") (pin "1") (pinfunction "1_1") (pintype "passive"))
      (node (ref "J4") (pin "1") (pinfunction "1_1") (pintype "passive"))
      (node (ref "Q2") (pin "S") (pinfunction "S_S") (pintype "passive"))
      (node (ref "Q2B") (pin "S") (pinfunction "S_S") (pintype "passive"))
      (node (ref "Q3") (pin "S") (pinfunction "S_S") (pintype "passive"))
      (node (ref "Q3B") (pin "S") (pinfunction "S_S") (pintype "passive"))
      (node (ref "SB1") (pin "2") (pinfunction "2_2") (pintype "passive"))
      (node (ref "U1") (pin "25") (pinfunction "PGND_25") (pintype "passive"))
      (node (ref "U1") (pin "33") (pinfunction "PGND_33") (pintype "passive"))
    )
    (net (code "48") (name "unconnected-(H1-Pad1)") (class "Default")
      (node (ref "H1") (pin "1") (pinfunction "1_1") (pintype "passive+no_connect"))
    )
    (net (code "49") (name "unconnected-(H2-Pad1)") (class "Default")
      (node (ref "H2") (pin "1") (pinfunction "1_1") (pintype "passive+no_connect"))
    )
    (net (code "50") (name "unconnected-(H3-Pad1)") (class "Default")
      (node (ref "H3") (pin "1") (pinfunction "1_1") (pintype "passive+no_connect"))
    )
    (net (code "51") (name "unconnected-(H4-Pad1)") (class "Default")
      (node (ref "H4") (pin "1") (pinfunction "1_1") (pintype "passive+no_connect"))
    )
    (net (code "52") (name "unconnected-(U1-NC-Pad2)") (class "Default")
      (node (ref "U1") (pin "2") (pinfunction "NC_2") (pintype "passive+no_connect"))
    )
    (net (code "53") (name "unconnected-(U1-NC-Pad7)") (class "Default")
      (node (ref "U1") (pin "7") (pinfunction "NC_7") (pintype "passive+no_connect"))
    )
    (net (code "54") (name "unconnected-(U1-NC-Pad9)") (class "Default")
      (node (ref "U1") (pin "9") (pinfunction "NC_9") (pintype "passive+no_connect"))
    )
    (net (code "55") (name "unconnected-(U1-NC-Pad13)") (class "Default")
      (node (ref "U1") (pin "13") (pinfunction "NC_13") (pintype "passive+no_connect"))
    )
  )
)
